# PGTN_daisy2_controls.net
KiCad netlist of a schematic drawn in EAGLE
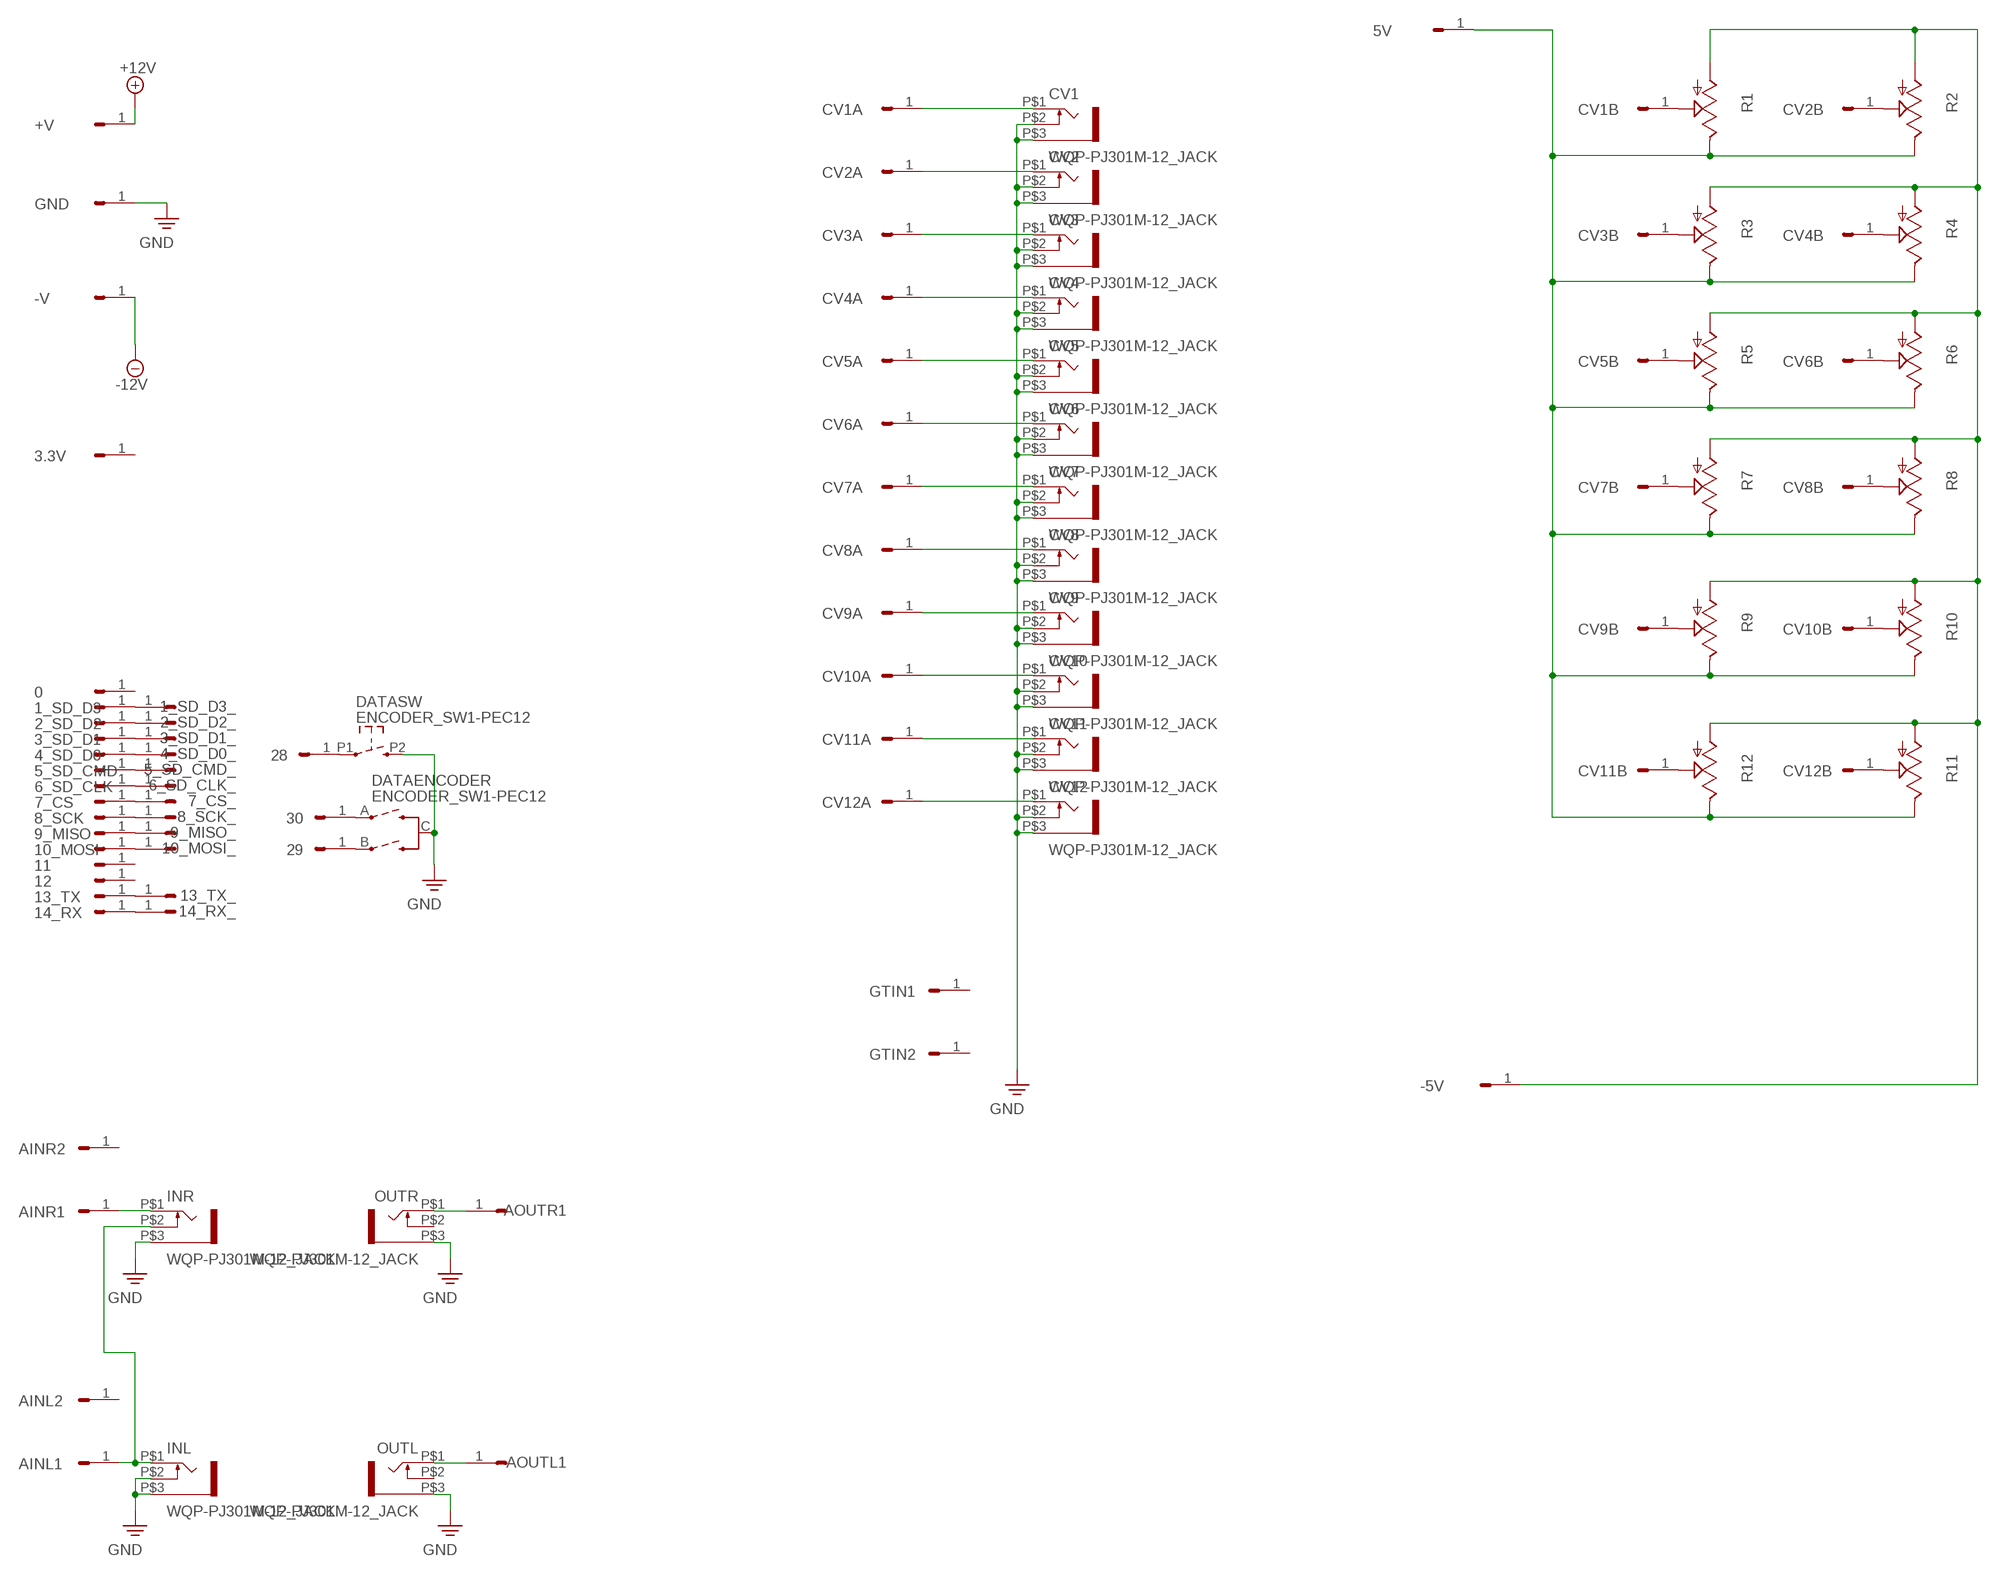
[diagram p0: schematic, sheet 1]

(export (version "E")
  (design (tool "Eeschema 10.0.6"))
  (components
    (comp (ref "+V")
      (value "HEADER/MALE/01")
      (footprint "eagle-import:HEADER_MALE_01")
      (fields (field (name "SPICEPREFIX") "X"))
      (libsource (lib "eagle-import") (part "HEADER/MALE/01"))
    )
    (comp (ref "-5V")
      (value "HEADER/MALE/01")
      (footprint "eagle-import:HEADER_MALE_01")
      (fields (field (name "SPICEPREFIX") "X"))
      (libsource (lib "eagle-import") (part "HEADER/MALE/01"))
    )
    (comp (ref "-V")
      (value "HEADER/MALE/01")
      (footprint "eagle-import:HEADER_MALE_01")
      (fields (field (name "SPICEPREFIX") "X"))
      (libsource (lib "eagle-import") (part "HEADER/MALE/01"))
    )
    (comp (ref "0")
      (value "HEADER/MALE/01")
      (footprint "eagle-import:HEADER_MALE_01")
      (fields (field (name "SPICEPREFIX") "X"))
      (libsource (lib "eagle-import") (part "HEADER/MALE/01"))
    )
    (comp (ref "1_SD_D3")
      (value "HEADER/MALE/01")
      (footprint "eagle-import:HEADER_MALE_01")
      (fields (field (name "SPICEPREFIX") "X"))
      (libsource (lib "eagle-import") (part "HEADER/MALE/01"))
    )
    (comp (ref "1_SD_D3_")
      (value "HEADER/MALE/01")
      (footprint "eagle-import:HEADER_MALE_01")
      (fields (field (name "SPICEPREFIX") "X"))
      (libsource (lib "eagle-import") (part "HEADER/MALE/01"))
    )
    (comp (ref "2_SD_D2")
      (value "HEADER/MALE/01")
      (footprint "eagle-import:HEADER_MALE_01")
      (fields (field (name "SPICEPREFIX") "X"))
      (libsource (lib "eagle-import") (part "HEADER/MALE/01"))
    )
    (comp (ref "2_SD_D2_")
      (value "HEADER/MALE/01")
      (footprint "eagle-import:HEADER_MALE_01")
      (fields (field (name "SPICEPREFIX") "X"))
      (libsource (lib "eagle-import") (part "HEADER/MALE/01"))
    )
    (comp (ref "3.3V")
      (value "HEADER/MALE/01")
      (footprint "eagle-import:HEADER_MALE_01")
      (fields (field (name "SPICEPREFIX") "X"))
      (libsource (lib "eagle-import") (part "HEADER/MALE/01"))
    )
    (comp (ref "3_SD_D1")
      (value "HEADER/MALE/01")
      (footprint "eagle-import:HEADER_MALE_01")
      (fields (field (name "SPICEPREFIX") "X"))
      (libsource (lib "eagle-import") (part "HEADER/MALE/01"))
    )
    (comp (ref "3_SD_D1_")
      (value "HEADER/MALE/01")
      (footprint "eagle-import:HEADER_MALE_01")
      (fields (field (name "SPICEPREFIX") "X"))
      (libsource (lib "eagle-import") (part "HEADER/MALE/01"))
    )
    (comp (ref "4_SD_D0")
      (value "HEADER/MALE/01")
      (footprint "eagle-import:HEADER_MALE_01")
      (fields (field (name "SPICEPREFIX") "X"))
      (libsource (lib "eagle-import") (part "HEADER/MALE/01"))
    )
    (comp (ref "4_SD_D0_")
      (value "HEADER/MALE/01")
      (footprint "eagle-import:HEADER_MALE_01")
      (fields (field (name "SPICEPREFIX") "X"))
      (libsource (lib "eagle-import") (part "HEADER/MALE/01"))
    )
    (comp (ref "5V")
      (value "HEADER/MALE/01")
      (footprint "eagle-import:HEADER_MALE_01")
      (fields (field (name "SPICEPREFIX") "X"))
      (libsource (lib "eagle-import") (part "HEADER/MALE/01"))
    )
    (comp (ref "5_SD_CMD")
      (value "HEADER/MALE/01")
      (footprint "eagle-import:HEADER_MALE_01")
      (fields (field (name "SPICEPREFIX") "X"))
      (libsource (lib "eagle-import") (part "HEADER/MALE/01"))
    )
    (comp (ref "5_SD_CMD_")
      (value "HEADER/MALE/01")
      (footprint "eagle-import:HEADER_MALE_01")
      (fields (field (name "SPICEPREFIX") "X"))
      (libsource (lib "eagle-import") (part "HEADER/MALE/01"))
    )
    (comp (ref "6_SD_CLK")
      (value "HEADER/MALE/01")
      (footprint "eagle-import:HEADER_MALE_01")
      (fields (field (name "SPICEPREFIX") "X"))
      (libsource (lib "eagle-import") (part "HEADER/MALE/01"))
    )
    (comp (ref "6_SD_CLK_")
      (value "HEADER/MALE/01")
      (footprint "eagle-import:HEADER_MALE_01")
      (fields (field (name "SPICEPREFIX") "X"))
      (libsource (lib "eagle-import") (part "HEADER/MALE/01"))
    )
    (comp (ref "7_CS")
      (value "HEADER/MALE/01")
      (footprint "eagle-import:HEADER_MALE_01")
      (fields (field (name "SPICEPREFIX") "X"))
      (libsource (lib "eagle-import") (part "HEADER/MALE/01"))
    )
    (comp (ref "7_CS_")
      (value "HEADER/MALE/01")
      (footprint "eagle-import:HEADER_MALE_01")
      (fields (field (name "SPICEPREFIX") "X"))
      (libsource (lib "eagle-import") (part "HEADER/MALE/01"))
    )
    (comp (ref "8_SCK")
      (value "HEADER/MALE/01")
      (footprint "eagle-import:HEADER_MALE_01")
      (fields (field (name "SPICEPREFIX") "X"))
      (libsource (lib "eagle-import") (part "HEADER/MALE/01"))
    )
    (comp (ref "8_SCK_")
      (value "HEADER/MALE/01")
      (footprint "eagle-import:HEADER_MALE_01")
      (fields (field (name "SPICEPREFIX") "X"))
      (libsource (lib "eagle-import") (part "HEADER/MALE/01"))
    )
    (comp (ref "9_MISO")
      (value "HEADER/MALE/01")
      (footprint "eagle-import:HEADER_MALE_01")
      (fields (field (name "SPICEPREFIX") "X"))
      (libsource (lib "eagle-import") (part "HEADER/MALE/01"))
    )
    (comp (ref "9_MISO_")
      (value "HEADER/MALE/01")
      (footprint "eagle-import:HEADER_MALE_01")
      (fields (field (name "SPICEPREFIX") "X"))
      (libsource (lib "eagle-import") (part "HEADER/MALE/01"))
    )
    (comp (ref "10_MOSI")
      (value "HEADER/MALE/01")
      (footprint "eagle-import:HEADER_MALE_01")
      (fields (field (name "SPICEPREFIX") "X"))
      (libsource (lib "eagle-import") (part "HEADER/MALE/01"))
    )
    (comp (ref "10_MOSI_")
      (value "HEADER/MALE/01")
      (footprint "eagle-import:HEADER_MALE_01")
      (fields (field (name "SPICEPREFIX") "X"))
      (libsource (lib "eagle-import") (part "HEADER/MALE/01"))
    )
    (comp (ref "11")
      (value "HEADER/MALE/01")
      (footprint "eagle-import:HEADER_MALE_01")
      (fields (field (name "SPICEPREFIX") "X"))
      (libsource (lib "eagle-import") (part "HEADER/MALE/01"))
    )
    (comp (ref "12")
      (value "HEADER/MALE/01")
      (footprint "eagle-import:HEADER_MALE_01")
      (fields (field (name "SPICEPREFIX") "X"))
      (libsource (lib "eagle-import") (part "HEADER/MALE/01"))
    )
    (comp (ref "13_TX")
      (value "HEADER/MALE/01")
      (footprint "eagle-import:HEADER_MALE_01")
      (fields (field (name "SPICEPREFIX") "X"))
      (libsource (lib "eagle-import") (part "HEADER/MALE/01"))
    )
    (comp (ref "13_TX_")
      (value "HEADER/MALE/01")
      (footprint "eagle-import:HEADER_MALE_01")
      (fields (field (name "SPICEPREFIX") "X"))
      (libsource (lib "eagle-import") (part "HEADER/MALE/01"))
    )
    (comp (ref "14_RX")
      (value "HEADER/MALE/01")
      (footprint "eagle-import:HEADER_MALE_01")
      (fields (field (name "SPICEPREFIX") "X"))
      (libsource (lib "eagle-import") (part "HEADER/MALE/01"))
    )
    (comp (ref "14_RX_")
      (value "HEADER/MALE/01")
      (footprint "eagle-import:HEADER_MALE_01")
      (fields (field (name "SPICEPREFIX") "X"))
      (libsource (lib "eagle-import") (part "HEADER/MALE/01"))
    )
    (comp (ref "28")
      (value "HEADER/MALE/01")
      (footprint "eagle-import:HEADER_MALE_01")
      (fields (field (name "SPICEPREFIX") "X"))
      (libsource (lib "eagle-import") (part "HEADER/MALE/01"))
    )
    (comp (ref "29")
      (value "HEADER/MALE/01")
      (footprint "eagle-import:HEADER_MALE_01")
      (fields (field (name "SPICEPREFIX") "X"))
      (libsource (lib "eagle-import") (part "HEADER/MALE/01"))
    )
    (comp (ref "30")
      (value "HEADER/MALE/01")
      (footprint "eagle-import:HEADER_MALE_01")
      (fields (field (name "SPICEPREFIX") "X"))
      (libsource (lib "eagle-import") (part "HEADER/MALE/01"))
    )
    (comp (ref "AINL1")
      (value "HEADER/MALE/01")
      (footprint "eagle-import:HEADER_MALE_01")
      (fields (field (name "SPICEPREFIX") "X"))
      (libsource (lib "eagle-import") (part "HEADER/MALE/01"))
    )
    (comp (ref "AINL2")
      (value "HEADER/MALE/01")
      (footprint "eagle-import:HEADER_MALE_01")
      (fields (field (name "SPICEPREFIX") "X"))
      (libsource (lib "eagle-import") (part "HEADER/MALE/01"))
    )
    (comp (ref "AINR1")
      (value "HEADER/MALE/01")
      (footprint "eagle-import:HEADER_MALE_01")
      (fields (field (name "SPICEPREFIX") "X"))
      (libsource (lib "eagle-import") (part "HEADER/MALE/01"))
    )
    (comp (ref "AINR2")
      (value "HEADER/MALE/01")
      (footprint "eagle-import:HEADER_MALE_01")
      (fields (field (name "SPICEPREFIX") "X"))
      (libsource (lib "eagle-import") (part "HEADER/MALE/01"))
    )
    (comp (ref "AOUTL1")
      (value "HEADER/MALE/01")
      (footprint "eagle-import:HEADER_MALE_01")
      (fields (field (name "SPICEPREFIX") "X"))
      (libsource (lib "eagle-import") (part "HEADER/MALE/01"))
    )
    (comp (ref "AOUTR1")
      (value "HEADER/MALE/01")
      (footprint "eagle-import:HEADER_MALE_01")
      (fields (field (name "SPICEPREFIX") "X"))
      (libsource (lib "eagle-import") (part "HEADER/MALE/01"))
    )
    (comp (ref "CV1")
      (value "WQP-PJ301M-12_JACK")
      (footprint "eagle-import:WQP-PJ301M-12_JACK")
      (libsource (lib "eagle-import") (part "WQP-PJ301M-12_JACK"))
    )
    (comp (ref "CV1A")
      (value "HEADER/MALE/01")
      (footprint "eagle-import:HEADER_MALE_01")
      (fields (field (name "SPICEPREFIX") "X"))
      (libsource (lib "eagle-import") (part "HEADER/MALE/01"))
    )
    (comp (ref "CV1B")
      (value "HEADER/MALE/01")
      (footprint "eagle-import:HEADER_MALE_01")
      (fields (field (name "SPICEPREFIX") "X"))
      (libsource (lib "eagle-import") (part "HEADER/MALE/01"))
    )
    (comp (ref "CV2")
      (value "WQP-PJ301M-12_JACK")
      (footprint "eagle-import:WQP-PJ301M-12_JACK")
      (libsource (lib "eagle-import") (part "WQP-PJ301M-12_JACK"))
    )
    (comp (ref "CV2A")
      (value "HEADER/MALE/01")
      (footprint "eagle-import:HEADER_MALE_01")
      (fields (field (name "SPICEPREFIX") "X"))
      (libsource (lib "eagle-import") (part "HEADER/MALE/01"))
    )
    (comp (ref "CV2B")
      (value "HEADER/MALE/01")
      (footprint "eagle-import:HEADER_MALE_01")
      (fields (field (name "SPICEPREFIX") "X"))
      (libsource (lib "eagle-import") (part "HEADER/MALE/01"))
    )
    (comp (ref "CV3")
      (value "WQP-PJ301M-12_JACK")
      (footprint "eagle-import:WQP-PJ301M-12_JACK")
      (libsource (lib "eagle-import") (part "WQP-PJ301M-12_JACK"))
    )
    (comp (ref "CV3A")
      (value "HEADER/MALE/01")
      (footprint "eagle-import:HEADER_MALE_01")
      (fields (field (name "SPICEPREFIX") "X"))
      (libsource (lib "eagle-import") (part "HEADER/MALE/01"))
    )
    (comp (ref "CV3B")
      (value "HEADER/MALE/01")
      (footprint "eagle-import:HEADER_MALE_01")
      (fields (field (name "SPICEPREFIX") "X"))
      (libsource (lib "eagle-import") (part "HEADER/MALE/01"))
    )
    (comp (ref "CV4")
      (value "WQP-PJ301M-12_JACK")
      (footprint "eagle-import:WQP-PJ301M-12_JACK")
      (libsource (lib "eagle-import") (part "WQP-PJ301M-12_JACK"))
    )
    (comp (ref "CV4A")
      (value "HEADER/MALE/01")
      (footprint "eagle-import:HEADER_MALE_01")
      (fields (field (name "SPICEPREFIX") "X"))
      (libsource (lib "eagle-import") (part "HEADER/MALE/01"))
    )
    (comp (ref "CV4B")
      (value "HEADER/MALE/01")
      (footprint "eagle-import:HEADER_MALE_01")
      (fields (field (name "SPICEPREFIX") "X"))
      (libsource (lib "eagle-import") (part "HEADER/MALE/01"))
    )
    (comp (ref "CV5")
      (value "WQP-PJ301M-12_JACK")
      (footprint "eagle-import:WQP-PJ301M-12_JACK")
      (libsource (lib "eagle-import") (part "WQP-PJ301M-12_JACK"))
    )
    (comp (ref "CV5A")
      (value "HEADER/MALE/01")
      (footprint "eagle-import:HEADER_MALE_01")
      (fields (field (name "SPICEPREFIX") "X"))
      (libsource (lib "eagle-import") (part "HEADER/MALE/01"))
    )
    (comp (ref "CV5B")
      (value "HEADER/MALE/01")
      (footprint "eagle-import:HEADER_MALE_01")
      (fields (field (name "SPICEPREFIX") "X"))
      (libsource (lib "eagle-import") (part "HEADER/MALE/01"))
    )
    (comp (ref "CV6")
      (value "WQP-PJ301M-12_JACK")
      (footprint "eagle-import:WQP-PJ301M-12_JACK")
      (libsource (lib "eagle-import") (part "WQP-PJ301M-12_JACK"))
    )
    (comp (ref "CV6A")
      (value "HEADER/MALE/01")
      (footprint "eagle-import:HEADER_MALE_01")
      (fields (field (name "SPICEPREFIX") "X"))
      (libsource (lib "eagle-import") (part "HEADER/MALE/01"))
    )
    (comp (ref "CV6B")
      (value "HEADER/MALE/01")
      (footprint "eagle-import:HEADER_MALE_01")
      (fields (field (name "SPICEPREFIX") "X"))
      (libsource (lib "eagle-import") (part "HEADER/MALE/01"))
    )
    (comp (ref "CV7")
      (value "WQP-PJ301M-12_JACK")
      (footprint "eagle-import:WQP-PJ301M-12_JACK")
      (libsource (lib "eagle-import") (part "WQP-PJ301M-12_JACK"))
    )
    (comp (ref "CV7A")
      (value "HEADER/MALE/01")
      (footprint "eagle-import:HEADER_MALE_01")
      (fields (field (name "SPICEPREFIX") "X"))
      (libsource (lib "eagle-import") (part "HEADER/MALE/01"))
    )
    (comp (ref "CV7B")
      (value "HEADER/MALE/01")
      (footprint "eagle-import:HEADER_MALE_01")
      (fields (field (name "SPICEPREFIX") "X"))
      (libsource (lib "eagle-import") (part "HEADER/MALE/01"))
    )
    (comp (ref "CV8")
      (value "WQP-PJ301M-12_JACK")
      (footprint "eagle-import:WQP-PJ301M-12_JACK")
      (libsource (lib "eagle-import") (part "WQP-PJ301M-12_JACK"))
    )
    (comp (ref "CV8A")
      (value "HEADER/MALE/01")
      (footprint "eagle-import:HEADER_MALE_01")
      (fields (field (name "SPICEPREFIX") "X"))
      (libsource (lib "eagle-import") (part "HEADER/MALE/01"))
    )
    (comp (ref "CV8B")
      (value "HEADER/MALE/01")
      (footprint "eagle-import:HEADER_MALE_01")
      (fields (field (name "SPICEPREFIX") "X"))
      (libsource (lib "eagle-import") (part "HEADER/MALE/01"))
    )
    (comp (ref "CV9")
      (value "WQP-PJ301M-12_JACK")
      (footprint "eagle-import:WQP-PJ301M-12_JACK")
      (libsource (lib "eagle-import") (part "WQP-PJ301M-12_JACK"))
    )
    (comp (ref "CV9A")
      (value "HEADER/MALE/01")
      (footprint "eagle-import:HEADER_MALE_01")
      (fields (field (name "SPICEPREFIX") "X"))
      (libsource (lib "eagle-import") (part "HEADER/MALE/01"))
    )
    (comp (ref "CV9B")
      (value "HEADER/MALE/01")
      (footprint "eagle-import:HEADER_MALE_01")
      (fields (field (name "SPICEPREFIX") "X"))
      (libsource (lib "eagle-import") (part "HEADER/MALE/01"))
    )
    (comp (ref "CV10")
      (value "WQP-PJ301M-12_JACK")
      (footprint "eagle-import:WQP-PJ301M-12_JACK")
      (libsource (lib "eagle-import") (part "WQP-PJ301M-12_JACK"))
    )
    (comp (ref "CV10A")
      (value "HEADER/MALE/01")
      (footprint "eagle-import:HEADER_MALE_01")
      (fields (field (name "SPICEPREFIX") "X"))
      (libsource (lib "eagle-import") (part "HEADER/MALE/01"))
    )
    (comp (ref "CV10B")
      (value "HEADER/MALE/01")
      (footprint "eagle-import:HEADER_MALE_01")
      (fields (field (name "SPICEPREFIX") "X"))
      (libsource (lib "eagle-import") (part "HEADER/MALE/01"))
    )
    (comp (ref "CV11")
      (value "WQP-PJ301M-12_JACK")
      (footprint "eagle-import:WQP-PJ301M-12_JACK")
      (libsource (lib "eagle-import") (part "WQP-PJ301M-12_JACK"))
    )
    (comp (ref "CV11A")
      (value "HEADER/MALE/01")
      (footprint "eagle-import:HEADER_MALE_01")
      (fields (field (name "SPICEPREFIX") "X"))
      (libsource (lib "eagle-import") (part "HEADER/MALE/01"))
    )
    (comp (ref "CV11B")
      (value "HEADER/MALE/01")
      (footprint "eagle-import:HEADER_MALE_01")
      (fields (field (name "SPICEPREFIX") "X"))
      (libsource (lib "eagle-import") (part "HEADER/MALE/01"))
    )
    (comp (ref "CV12")
      (value "WQP-PJ301M-12_JACK")
      (footprint "eagle-import:WQP-PJ301M-12_JACK")
      (libsource (lib "eagle-import") (part "WQP-PJ301M-12_JACK"))
    )
    (comp (ref "CV12A")
      (value "HEADER/MALE/01")
      (footprint "eagle-import:HEADER_MALE_01")
      (fields (field (name "SPICEPREFIX") "X"))
      (libsource (lib "eagle-import") (part "HEADER/MALE/01"))
    )
    (comp (ref "CV12B")
      (value "HEADER/MALE/01")
      (footprint "eagle-import:HEADER_MALE_01")
      (fields (field (name "SPICEPREFIX") "X"))
      (libsource (lib "eagle-import") (part "HEADER/MALE/01"))
    )
    (comp (ref "DATA")
      (value "ENCODER_SW1-PEC12")
      (footprint "eagle-import:PEC12_INCREMENTAL_ENCODER")
      (libsource (lib "eagle-import") (part "ENCODER_SW1-PEC12"))
    )
    (comp (ref "GND")
      (value "HEADER/MALE/01")
      (footprint "eagle-import:HEADER_MALE_01")
      (fields (field (name "SPICEPREFIX") "X"))
      (libsource (lib "eagle-import") (part "HEADER/MALE/01"))
    )
    (comp (ref "GTIN1")
      (value "HEADER/MALE/01")
      (footprint "eagle-import:HEADER_MALE_01")
      (fields (field (name "SPICEPREFIX") "X"))
      (libsource (lib "eagle-import") (part "HEADER/MALE/01"))
    )
    (comp (ref "GTIN2")
      (value "HEADER/MALE/01")
      (footprint "eagle-import:HEADER_MALE_01")
      (fields (field (name "SPICEPREFIX") "X"))
      (libsource (lib "eagle-import") (part "HEADER/MALE/01"))
    )
    (comp (ref "INL")
      (value "WQP-PJ301M-12_JACK")
      (footprint "eagle-import:WQP-PJ301M-12_JACK")
      (libsource (lib "eagle-import") (part "WQP-PJ301M-12_JACK"))
    )
    (comp (ref "INR")
      (value "WQP-PJ301M-12_JACK")
      (footprint "eagle-import:WQP-PJ301M-12_JACK")
      (libsource (lib "eagle-import") (part "WQP-PJ301M-12_JACK"))
    )
    (comp (ref "OUTL")
      (value "WQP-PJ301M-12_JACK")
      (footprint "eagle-import:WQP-PJ301M-12_JACK")
      (libsource (lib "eagle-import") (part "WQP-PJ301M-12_JACK"))
    )
    (comp (ref "OUTR")
      (value "WQP-PJ301M-12_JACK")
      (footprint "eagle-import:WQP-PJ301M-12_JACK")
      (libsource (lib "eagle-import") (part "WQP-PJ301M-12_JACK"))
    )
    (comp (ref "R1")
      (value "9MM_SNAP-IN_POT_")
      (footprint "eagle-import:9MM_SNAP-IN_POT")
      (libsource (lib "eagle-import") (part "9MM_SNAP-IN_POT_"))
    )
    (comp (ref "R2")
      (value "9MM_SNAP-IN_POT_")
      (footprint "eagle-import:9MM_SNAP-IN_POT")
      (libsource (lib "eagle-import") (part "9MM_SNAP-IN_POT_"))
    )
    (comp (ref "R3")
      (value "9MM_SNAP-IN_POT_")
      (footprint "eagle-import:9MM_SNAP-IN_POT")
      (libsource (lib "eagle-import") (part "9MM_SNAP-IN_POT_"))
    )
    (comp (ref "R4")
      (value "9MM_SNAP-IN_POT_")
      (footprint "eagle-import:9MM_SNAP-IN_POT")
      (libsource (lib "eagle-import") (part "9MM_SNAP-IN_POT_"))
    )
    (comp (ref "R5")
      (value "9MM_SNAP-IN_POT_")
      (footprint "eagle-import:9MM_SNAP-IN_POT")
      (libsource (lib "eagle-import") (part "9MM_SNAP-IN_POT_"))
    )
    (comp (ref "R6")
      (value "9MM_SNAP-IN_POT_")
      (footprint "eagle-import:9MM_SNAP-IN_POT")
      (libsource (lib "eagle-import") (part "9MM_SNAP-IN_POT_"))
    )
    (comp (ref "R7")
      (value "9MM_SNAP-IN_POT_")
      (footprint "eagle-import:9MM_SNAP-IN_POT")
      (libsource (lib "eagle-import") (part "9MM_SNAP-IN_POT_"))
    )
    (comp (ref "R8")
      (value "9MM_SNAP-IN_POT_")
      (footprint "eagle-import:9MM_SNAP-IN_POT")
      (libsource (lib "eagle-import") (part "9MM_SNAP-IN_POT_"))
    )
    (comp (ref "R9")
      (value "9MM_SNAP-IN_POT_")
      (footprint "eagle-import:9MM_SNAP-IN_POT")
      (libsource (lib "eagle-import") (part "9MM_SNAP-IN_POT_"))
    )
    (comp (ref "R10")
      (value "9MM_SNAP-IN_POT_")
      (footprint "eagle-import:9MM_SNAP-IN_POT")
      (libsource (lib "eagle-import") (part "9MM_SNAP-IN_POT_"))
    )
    (comp (ref "R11")
      (value "9MM_SNAP-IN_POT_")
      (footprint "eagle-import:9MM_SNAP-IN_POT")
      (libsource (lib "eagle-import") (part "9MM_SNAP-IN_POT_"))
    )
    (comp (ref "R12")
      (value "9MM_SNAP-IN_POT_")
      (footprint "eagle-import:9MM_SNAP-IN_POT")
      (libsource (lib "eagle-import") (part "9MM_SNAP-IN_POT_"))
    )
  )
  (nets
    (net (code "1") (name "+12V") (class "Default")
      (node (ref "+V") (pin "1") (pinfunction "3_1") (pintype "passive"))
    )
    (net (code "2") (name "-12V") (class "Default")
      (node (ref "-V") (pin "1") (pinfunction "3_1") (pintype "passive"))
    )
    (net (code "3") (name "GND") (class "Default")
      (node (ref "CV1") (pin "P$2") (pinfunction "3_P$2") (pintype "passive"))
      (node (ref "CV1") (pin "P$3") (pinfunction "1_P$3") (pintype "passive"))
      (node (ref "CV10") (pin "P$2") (pinfunction "3_P$2") (pintype "passive"))
      (node (ref "CV10") (pin "P$3") (pinfunction "1_P$3") (pintype "passive"))
      (node (ref "CV11") (pin "P$2") (pinfunction "3_P$2") (pintype "passive"))
      (node (ref "CV11") (pin "P$3") (pinfunction "1_P$3") (pintype "passive"))
      (node (ref "CV12") (pin "P$2") (pinfunction "3_P$2") (pintype "passive"))
      (node (ref "CV12") (pin "P$3") (pinfunction "1_P$3") (pintype "passive"))
      (node (ref "CV2") (pin "P$2") (pinfunction "3_P$2") (pintype "passive"))
      (node (ref "CV2") (pin "P$3") (pinfunction "1_P$3") (pintype "passive"))
      (node (ref "CV3") (pin "P$2") (pinfunction "3_P$2") (pintype "passive"))
      (node (ref "CV3") (pin "P$3") (pinfunction "1_P$3") (pintype "passive"))
      (node (ref "CV4") (pin "P$2") (pinfunction "3_P$2") (pintype "passive"))
      (node (ref "CV4") (pin "P$3") (pinfunction "1_P$3") (pintype "passive"))
      (node (ref "CV5") (pin "P$2") (pinfunction "3_P$2") (pintype "passive"))
      (node (ref "CV5") (pin "P$3") (pinfunction "1_P$3") (pintype "passive"))
      (node (ref "CV6") (pin "P$2") (pinfunction "3_P$2") (pintype "passive"))
      (node (ref "CV6") (pin "P$3") (pinfunction "1_P$3") (pintype "passive"))
      (node (ref "CV7") (pin "P$2") (pinfunction "3_P$2") (pintype "passive"))
      (node (ref "CV7") (pin "P$3") (pinfunction "1_P$3") (pintype "passive"))
      (node (ref "CV8") (pin "P$2") (pinfunction "3_P$2") (pintype "passive"))
      (node (ref "CV8") (pin "P$3") (pinfunction "1_P$3") (pintype "passive"))
      (node (ref "CV9") (pin "P$2") (pinfunction "3_P$2") (pintype "passive"))
      (node (ref "CV9") (pin "P$3") (pinfunction "1_P$3") (pintype "passive"))
      (node (ref "DATA") (pin "C") (pinfunction "C_C") (pintype "passive"))
      (node (ref "DATA") (pin "P2") (pinfunction "2_P2") (pintype "passive"))
      (node (ref "GND") (pin "1") (pinfunction "3_1") (pintype "passive"))
      (node (ref "INL") (pin "P$2") (pinfunction "3_P$2") (pintype "passive"))
      (node (ref "INL") (pin "P$3") (pinfunction "1_P$3") (pintype "passive"))
      (node (ref "INR") (pin "P$3") (pinfunction "1_P$3") (pintype "passive"))
      (node (ref "OUTL") (pin "P$3") (pinfunction "1_P$3") (pintype "passive"))
      (node (ref "OUTR") (pin "P$3") (pinfunction "1_P$3") (pintype "passive"))
    )
    (net (code "4") (name "Net-(-5V-3)") (class "Default")
      (node (ref "-5V") (pin "1") (pinfunction "3_1") (pintype "passive"))
      (node (ref "R1") (pin "1") (pinfunction "A_1") (pintype "passive"))
      (node (ref "R10") (pin "1") (pinfunction "A_1") (pintype "passive"))
      (node (ref "R11") (pin "1") (pinfunction "A_1") (pintype "passive"))
      (node (ref "R12") (pin "1") (pinfunction "A_1") (pintype "passive"))
      (node (ref "R2") (pin "1") (pinfunction "A_1") (pintype "passive"))
      (node (ref "R3") (pin "1") (pinfunction "A_1") (pintype "passive"))
      (node (ref "R4") (pin "1") (pinfunction "A_1") (pintype "passive"))
      (node (ref "R5") (pin "1") (pinfunction "A_1") (pintype "passive"))
      (node (ref "R6") (pin "1") (pinfunction "A_1") (pintype "passive"))
      (node (ref "R7") (pin "1") (pinfunction "A_1") (pintype "passive"))
      (node (ref "R8") (pin "1") (pinfunction "A_1") (pintype "passive"))
      (node (ref "R9") (pin "1") (pinfunction "A_1") (pintype "passive"))
    )
    (net (code "5") (name "Net-(1_SD_D3-3)") (class "Default")
      (node (ref "1_SD_D3") (pin "1") (pinfunction "3_1") (pintype "passive"))
      (node (ref "1_SD_D3_") (pin "1") (pinfunction "3_1") (pintype "passive"))
    )
    (net (code "6") (name "Net-(2_SD_D2-3)") (class "Default")
      (node (ref "2_SD_D2") (pin "1") (pinfunction "3_1") (pintype "passive"))
      (node (ref "2_SD_D2_") (pin "1") (pinfunction "3_1") (pintype "passive"))
    )
    (net (code "7") (name "Net-(3_SD_D1-3)") (class "Default")
      (node (ref "3_SD_D1") (pin "1") (pinfunction "3_1") (pintype "passive"))
      (node (ref "3_SD_D1_") (pin "1") (pinfunction "3_1") (pintype "passive"))
    )
    (net (code "8") (name "Net-(4_SD_D0-3)") (class "Default")
      (node (ref "4_SD_D0") (pin "1") (pinfunction "3_1") (pintype "passive"))
      (node (ref "4_SD_D0_") (pin "1") (pinfunction "3_1") (pintype "passive"))
    )
    (net (code "9") (name "Net-(5V-3)") (class "Default")
      (node (ref "5V") (pin "1") (pinfunction "3_1") (pintype "passive"))
      (node (ref "R1") (pin "3") (pinfunction "E_3") (pintype "passive"))
      (node (ref "R10") (pin "3") (pinfunction "E_3") (pintype "passive"))
      (node (ref "R11") (pin "3") (pinfunction "E_3") (pintype "passive"))
      (node (ref "R12") (pin "3") (pinfunction "E_3") (pintype "passive"))
      (node (ref "R2") (pin "3") (pinfunction "E_3") (pintype "passive"))
      (node (ref "R3") (pin "3") (pinfunction "E_3") (pintype "passive"))
      (node (ref "R4") (pin "3") (pinfunction "E_3") (pintype "passive"))
      (node (ref "R5") (pin "3") (pinfunction "E_3") (pintype "passive"))
      (node (ref "R6") (pin "3") (pinfunction "E_3") (pintype "passive"))
      (node (ref "R7") (pin "3") (pinfunction "E_3") (pintype "passive"))
      (node (ref "R8") (pin "3") (pinfunction "E_3") (pintype "passive"))
      (node (ref "R9") (pin "3") (pinfunction "E_3") (pintype "passive"))
    )
    (net (code "10") (name "Net-(5_SD_CMD-3)") (class "Default")
      (node (ref "5_SD_CMD") (pin "1") (pinfunction "3_1") (pintype "passive"))
      (node (ref "5_SD_CMD_") (pin "1") (pinfunction "3_1") (pintype "passive"))
    )
    (net (code "11") (name "Net-(6_SD_CLK-3)") (class "Default")
      (node (ref "6_SD_CLK") (pin "1") (pinfunction "3_1") (pintype "passive"))
      (node (ref "6_SD_CLK_") (pin "1") (pinfunction "3_1") (pintype "passive"))
    )
    (net (code "12") (name "Net-(7_CS-3)") (class "Default")
      (node (ref "7_CS") (pin "1") (pinfunction "3_1") (pintype "passive"))
      (node (ref "7_CS_") (pin "1") (pinfunction "3_1") (pintype "passive"))
    )
    (net (code "13") (name "Net-(8_SCK-3)") (class "Default")
      (node (ref "8_SCK") (pin "1") (pinfunction "3_1") (pintype "passive"))
      (node (ref "8_SCK_") (pin "1") (pinfunction "3_1") (pintype "passive"))
    )
    (net (code "14") (name "Net-(9_MISO-3)") (class "Default")
      (node (ref "9_MISO") (pin "1") (pinfunction "3_1") (pintype "passive"))
      (node (ref "9_MISO_") (pin "1") (pinfunction "3_1") (pintype "passive"))
    )
    (net (code "15") (name "Net-(10_MOSI-3)") (class "Default")
      (node (ref "10_MOSI") (pin "1") (pinfunction "3_1") (pintype "passive"))
      (node (ref "10_MOSI_") (pin "1") (pinfunction "3_1") (pintype "passive"))
    )
    (net (code "16") (name "Net-(13_TX-3)") (class "Default")
      (node (ref "13_TX") (pin "1") (pinfunction "3_1") (pintype "passive"))
      (node (ref "13_TX_") (pin "1") (pinfunction "3_1") (pintype "passive"))
    )
    (net (code "17") (name "Net-(14_RX-3)") (class "Default")
      (node (ref "14_RX") (pin "1") (pinfunction "3_1") (pintype "passive"))
      (node (ref "14_RX_") (pin "1") (pinfunction "3_1") (pintype "passive"))
    )
    (net (code "18") (name "Net-(28-3)") (class "Default")
      (node (ref "28") (pin "1") (pinfunction "3_1") (pintype "passive"))
      (node (ref "DATA") (pin "P1") (pinfunction "1_P1") (pintype "passive"))
    )
    (net (code "19") (name "Net-(29-3)") (class "Default")
      (node (ref "29") (pin "1") (pinfunction "3_1") (pintype "passive"))
      (node (ref "DATA") (pin "B") (pinfunction "B_B") (pintype "passive"))
    )
    (net (code "20") (name "Net-(30-3)") (class "Default")
      (node (ref "30") (pin "1") (pinfunction "3_1") (pintype "passive"))
      (node (ref "DATA") (pin "A") (pinfunction "A_A") (pintype "passive"))
    )
    (net (code "21") (name "Net-(AINL1-3)") (class "Default")
      (node (ref "AINL1") (pin "1") (pinfunction "3_1") (pintype "passive"))
      (node (ref "INL") (pin "P$1") (pinfunction "2_P$1") (pintype "passive"))
      (node (ref "INR") (pin "P$2") (pinfunction "3_P$2") (pintype "passive"))
    )
    (net (code "22") (name "Net-(AINR1-3)") (class "Default")
      (node (ref "AINR1") (pin "1") (pinfunction "3_1") (pintype "passive"))
      (node (ref "INR") (pin "P$1") (pinfunction "2_P$1") (pintype "passive"))
    )
    (net (code "23") (name "Net-(AOUTL1-3)") (class "Default")
      (node (ref "AOUTL1") (pin "1") (pinfunction "3_1") (pintype "passive"))
      (node (ref "OUTL") (pin "P$1") (pinfunction "2_P$1") (pintype "passive"))
    )
    (net (code "24") (name "Net-(AOUTR1-3)") (class "Default")
      (node (ref "AOUTR1") (pin "1") (pinfunction "3_1") (pintype "passive"))
      (node (ref "OUTR") (pin "P$1") (pinfunction "2_P$1") (pintype "passive"))
    )
    (net (code "25") (name "Net-(CV1-2)") (class "Default")
      (node (ref "CV1") (pin "P$1") (pinfunction "2_P$1") (pintype "passive"))
      (node (ref "CV1A") (pin "1") (pinfunction "3_1") (pintype "passive"))
    )
    (net (code "26") (name "Net-(CV1B-3)") (class "Default")
      (node (ref "CV1B") (pin "1") (pinfunction "3_1") (pintype "passive"))
      (node (ref "R1") (pin "2") (pinfunction "S_2") (pintype "passive"))
    )
    (net (code "27") (name "Net-(CV2-2)") (class "Default")
      (node (ref "CV2") (pin "P$1") (pinfunction "2_P$1") (pintype "passive"))
      (node (ref "CV2A") (pin "1") (pinfunction "3_1") (pintype "passive"))
    )
    (net (code "28") (name "Net-(CV2B-3)") (class "Default")
      (node (ref "CV2B") (pin "1") (pinfunction "3_1") (pintype "passive"))
      (node (ref "R2") (pin "2") (pinfunction "S_2") (pintype "passive"))
    )
    (net (code "29") (name "Net-(CV3-2)") (class "Default")
      (node (ref "CV3") (pin "P$1") (pinfunction "2_P$1") (pintype "passive"))
      (node (ref "CV3A") (pin "1") (pinfunction "3_1") (pintype "passive"))
    )
    (net (code "30") (name "Net-(CV3B-3)") (class "Default")
      (node (ref "CV3B") (pin "1") (pinfunction "3_1") (pintype "passive"))
      (node (ref "R3") (pin "2") (pinfunction "S_2") (pintype "passive"))
    )
    (net (code "31") (name "Net-(CV4-2)") (class "Default")
      (node (ref "CV4") (pin "P$1") (pinfunction "2_P$1") (pintype "passive"))
      (node (ref "CV4A") (pin "1") (pinfunction "3_1") (pintype "passive"))
    )
    (net (code "32") (name "Net-(CV4B-3)") (class "Default")
      (node (ref "CV4B") (pin "1") (pinfunction "3_1") (pintype "passive"))
      (node (ref "R4") (pin "2") (pinfunction "S_2") (pintype "passive"))
    )
    (net (code "33") (name "Net-(CV5-2)") (class "Default")
      (node (ref "CV5") (pin "P$1") (pinfunction "2_P$1") (pintype "passive"))
      (node (ref "CV5A") (pin "1") (pinfunction "3_1") (pintype "passive"))
    )
    (net (code "34") (name "Net-(CV5B-3)") (class "Default")
      (node (ref "CV5B") (pin "1") (pinfunction "3_1") (pintype "passive"))
      (node (ref "R5") (pin "2") (pinfunction "S_2") (pintype "passive"))
    )
    (net (code "35") (name "Net-(CV6-2)") (class "Default")
      (node (ref "CV6") (pin "P$1") (pinfunction "2_P$1") (pintype "passive"))
      (node (ref "CV6A") (pin "1") (pinfunction "3_1") (pintype "passive"))
    )
    (net (code "36") (name "Net-(CV6B-3)") (class "Default")
      (node (ref "CV6B") (pin "1") (pinfunction "3_1") (pintype "passive"))
      (node (ref "R6") (pin "2") (pinfunction "S_2") (pintype "passive"))
    )
    (net (code "37") (name "Net-(CV7-2)") (class "Default")
      (node (ref "CV7") (pin "P$1") (pinfunction "2_P$1") (pintype "passive"))
      (node (ref "CV7A") (pin "1") (pinfunction "3_1") (pintype "passive"))
    )
    (net (code "38") (name "Net-(CV7B-3)") (class "Default")
      (node (ref "CV7B") (pin "1") (pinfunction "3_1") (pintype "passive"))
      (node (ref "R7") (pin "2") (pinfunction "S_2") (pintype "passive"))
    )
    (net (code "39") (name "Net-(CV8-2)") (class "Default")
      (node (ref "CV8") (pin "P$1") (pinfunction "2_P$1") (pintype "passive"))
      (node (ref "CV8A") (pin "1") (pinfunction "3_1") (pintype "passive"))
    )
    (net (code "40") (name "Net-(CV8B-3)") (class "Default")
      (node (ref "CV8B") (pin "1") (pinfunction "3_1") (pintype "passive"))
      (node (ref "R8") (pin "2") (pinfunction "S_2") (pintype "passive"))
    )
    (net (code "41") (name "Net-(CV9-2)") (class "Default")
      (node (ref "CV9") (pin "P$1") (pinfunction "2_P$1") (pintype "passive"))
      (node (ref "CV9A") (pin "1") (pinfunction "3_1") (pintype "passive"))
    )
    (net (code "42") (name "Net-(CV9B-3)") (class "Default")
      (node (ref "CV9B") (pin "1") (pinfunction "3_1") (pintype "passive"))
      (node (ref "R9") (pin "2") (pinfunction "S_2") (pintype "passive"))
    )
    (net (code "43") (name "Net-(CV10-2)") (class "Default")
      (node (ref "CV10") (pin "P$1") (pinfunction "2_P$1") (pintype "passive"))
      (node (ref "CV10A") (pin "1") (pinfunction "3_1") (pintype "passive"))
    )
    (net (code "44") (name "Net-(CV10B-3)") (class "Default")
      (node (ref "CV10B") (pin "1") (pinfunction "3_1") (pintype "passive"))
      (node (ref "R10") (pin "2") (pinfunction "S_2") (pintype "passive"))
    )
    (net (code "45") (name "Net-(CV11-2)") (class "Default")
      (node (ref "CV11") (pin "P$1") (pinfunction "2_P$1") (pintype "passive"))
      (node (ref "CV11A") (pin "1") (pinfunction "3_1") (pintype "passive"))
    )
    (net (code "46") (name "Net-(CV11B-3)") (class "Default")
      (node (ref "CV11B") (pin "1") (pinfunction "3_1") (pintype "passive"))
      (node (ref "R12") (pin "2") (pinfunction "S_2") (pintype "passive"))
    )
    (net (code "47") (name "Net-(CV12-2)") (class "Default")
      (node (ref "CV12") (pin "P$1") (pinfunction "2_P$1") (pintype "passive"))
      (node (ref "CV12A") (pin "1") (pinfunction "3_1") (pintype "passive"))
    )
    (net (code "48") (name "Net-(CV12B-3)") (class "Default")
      (node (ref "CV12B") (pin "1") (pinfunction "3_1") (pintype "passive"))
      (node (ref "R11") (pin "2") (pinfunction "S_2") (pintype "passive"))
    )
    (net (code "49") (name "unconnected-(0-3-Pad1)") (class "Default")
      (node (ref "0") (pin "1") (pinfunction "3_1") (pintype "passive"))
    )
    (net (code "50") (name "unconnected-(3.3V-3-Pad1)") (class "Default")
      (node (ref "3.3V") (pin "1") (pinfunction "3_1") (pintype "passive"))
    )
    (net (code "51") (name "unconnected-(11-3-Pad1)") (class "Default")
      (node (ref "11") (pin "1") (pinfunction "3_1") (pintype "passive"))
    )
    (net (code "52") (name "unconnected-(12-3-Pad1)") (class "Default")
      (node (ref "12") (pin "1") (pinfunction "3_1") (pintype "passive"))
    )
    (net (code "53") (name "unconnected-(AINL2-3-Pad1)") (class "Default")
      (node (ref "AINL2") (pin "1") (pinfunction "3_1") (pintype "passive"))
    )
    (net (code "54") (name "unconnected-(AINR2-3-Pad1)") (class "Default")
      (node (ref "AINR2") (pin "1") (pinfunction "3_1") (pintype "passive"))
    )
    (net (code "55") (name "unconnected-(GTIN1-3-Pad1)") (class "Default")
      (node (ref "GTIN1") (pin "1") (pinfunction "3_1") (pintype "passive"))
    )
    (net (code "56") (name "unconnected-(GTIN2-3-Pad1)") (class "Default")
      (node (ref "GTIN2") (pin "1") (pinfunction "3_1") (pintype "passive"))
    )
    (net (code "57") (name "unconnected-(OUTL-3-PadP$2)") (class "Default")
      (node (ref "OUTL") (pin "P$2") (pinfunction "3_P$2") (pintype "passive"))
    )
    (net (code "58") (name "unconnected-(OUTR-3-PadP$2)") (class "Default")
      (node (ref "OUTR") (pin "P$2") (pinfunction "3_P$2") (pintype "passive"))
    )
  )
)
